# Buck_converter_5V.net
KiCad netlist of a schematic drawn in Altium Designer
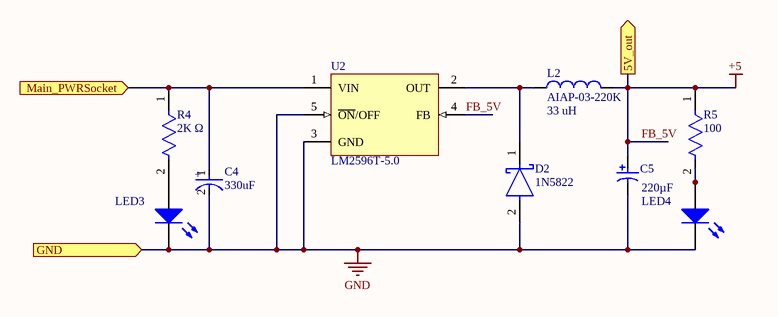
[diagram p0: Buck converter_5V.SchDoc]

(export (version "E")
  (design (tool "Eeschema 10.0.6"))
  (components
    (comp (ref "C4")
      (value "330uF")
      (footprint "FP-EEU-FC1V221L-MFG")
      (description "CAP ALUM 220UF 20% 35V RADIAL")
      (fields
        (field (name "OCTOPART") "https://octopart.com/eeu-fc1v221l-panasonic-39478519")
        (field (name "MANUFACTURER") "Panasonic Electronic Components")
      )
      (libsource (lib "Altium Content Vault") (part "385ce6c70a3ab0aa1e866f00bd8ed49"))
    )
    (comp (ref "C5")
      (value "EEU-FM1H221")
      (footprint "PNSC-EEUFM1H221-2")
      (description "Radial Lead Aluminum Electrolytic Capacitor, 220 uF, +/- 20%, 50 V, -40 to 105 degC, RoHS, Bulk")
      (fields (field (name "MANUFACTURER") "Panasonic") (field (name "CAPACITANCE") "220µF"))
      (libsource (lib "Altium Content Vault") (part "CAP-P-2"))
    )
    (comp (ref "D2")
      (value "1N5822")
      (footprint "FP-DO-201AD-MFG")
      (description "DIODE SCHOTTKY 40V 3A DO201AD")
      (fields
        (field (name "OCTOPART") "https://octopart.com/1n5822-stmicroelectronics-323225")
        (field (name "MANUFACTURER") "STMicroelectronics")
      )
      (libsource (lib "Altium Content Vault") (part "1d6ec82d83fb6aee721767c19dac4b9"))
    )
    (comp (ref "L2")
      (value "AIAP-03-220K")
      (footprint "ABRA-AIAP-02-2_V2")
      (fields
        (field (name "PARTNUMBER") "AIAP-02-102K")
        (field (name "INDUCTANCE") "33 uH")
        (field (name "TOLERANCE") "+/- 10%")
        (field (name "MANUFACTURER") "Abracon")
      )
      (libsource (lib "Altium Content Vault") (part "ABRA-IND-2"))
    )
    (comp (ref "LED3")
      (value "~")
      (footprint "Type 5mm")
      (description "THT LED round mono-color color lens, WL-TMRW, Bright Green")
      (fields (field (name "PARTNUMBER") "151051VS04000") (field (name "MANUFACTURER") "Wuerth Elektronik"))
      (libsource (lib "Altium Content Vault") (part "WE-LED_K1A2-2"))
    )
    (comp (ref "LED4")
      (value "~")
      (footprint "Type 5mm")
      (description "THT LED round mono-color color lens, WL-TMRW, Bright Green")
      (fields (field (name "PARTNUMBER") "151051VS04000") (field (name "MANUFACTURER") "Wuerth Elektronik"))
      (libsource (lib "Altium Content Vault") (part "WE-LED_K1A2-2"))
    )
    (comp (ref "R4")
      (value "2K Ω")
      (footprint "FP-MFR-25-MFG")
      (description "RES 1.18K OHM 1/4W 1% AXIAL")
      (fields (field (name "MANUFACTURER") "Yageo") (field (name "TOLERANCE") "1%"))
      (libsource (lib "Altium Content Vault") (part "1029c3af85768c4190bb7ad29bc67b5"))
    )
    (comp (ref "R5")
      (value "100")
      (footprint "FP-MFR-25-MFG")
      (description "RES 1.18K OHM 1/4W 1% AXIAL")
      (fields (field (name "MANUFACTURER") "Yageo") (field (name "TOLERANCE") "1%"))
      (libsource (lib "Altium Content Vault") (part "1029c3af85768c4190bb7ad29bc67b5"))
    )
    (comp (ref "U2")
      (value "LM2596T-5.0")
      (footprint "NDH0005A")
      (description "SIMPLE SWITCHER® Power Converter 150 KHz 3A Step-Down Voltage Regulator, 5-pin TO-220")
      (fields (field (name "MANUFACTURER") "Texas Instruments"))
      (libsource (lib "Altium Content Vault") (part "PM-REG-LM2575HVT-12"))
    )
  )
  (nets
    (net (code "1") (name "+5") (class "Default")
      (node (ref "C5") (pin "1") (pinfunction "1_1") (pintype "passive"))
      (node (ref "L2") (pin "2") (pinfunction "2_2") (pintype "passive"))
      (node (ref "R5") (pin "1") (pinfunction "1_1") (pintype "passive"))
      (node (ref "U2") (pin "4") (pinfunction "FB_4") (pintype "input"))
    )
    (net (code "2") (name "/Main_PWRSocket") (class "Default")
      (node (ref "C4") (pin "1") (pinfunction "C_1") (pintype "passive"))
      (node (ref "R4") (pin "1") (pinfunction "1_1") (pintype "passive"))
      (node (ref "U2") (pin "1") (pinfunction "VIN_1") (pintype "power_in"))
    )
    (net (code "3") (name "GND") (class "Default")
      (node (ref "C4") (pin "2") (pinfunction "A_2") (pintype "passive"))
      (node (ref "C5") (pin "2") (pinfunction "2_2") (pintype "passive"))
      (node (ref "D2") (pin "2") (pinfunction "A_2") (pintype "passive"))
      (node (ref "LED3") (pin "1") (pinfunction "K_1") (pintype "passive"))
      (node (ref "LED4") (pin "1") (pinfunction "K_1") (pintype "passive"))
      (node (ref "U2") (pin "3") (pinfunction "GND_3") (pintype "power_in"))
      (node (ref "U2") (pin "5") (pinfunction "~{ON}/OFF_5") (pintype "input"))
    )
    (net (code "4") (name "Net-(D2-C)") (class "Default")
      (node (ref "D2") (pin "1") (pinfunction "C_1") (pintype "passive"))
      (node (ref "L2") (pin "1") (pinfunction "1_1") (pintype "passive"))
      (node (ref "U2") (pin "2") (pinfunction "OUT_2") (pintype "power_in"))
    )
    (net (code "5") (name "Net-(LED3-A)") (class "Default")
      (node (ref "LED3") (pin "2") (pinfunction "A_2") (pintype "passive"))
      (node (ref "R4") (pin "2") (pinfunction "2_2") (pintype "passive"))
    )
    (net (code "6") (name "Net-(LED4-A)") (class "Default")
      (node (ref "LED4") (pin "2") (pinfunction "A_2") (pintype "passive"))
      (node (ref "R5") (pin "2") (pinfunction "2_2") (pintype "passive"))
    )
  )
)
